# FanTimer.net
KiCad netlist of a schematic drawn in EAGLE
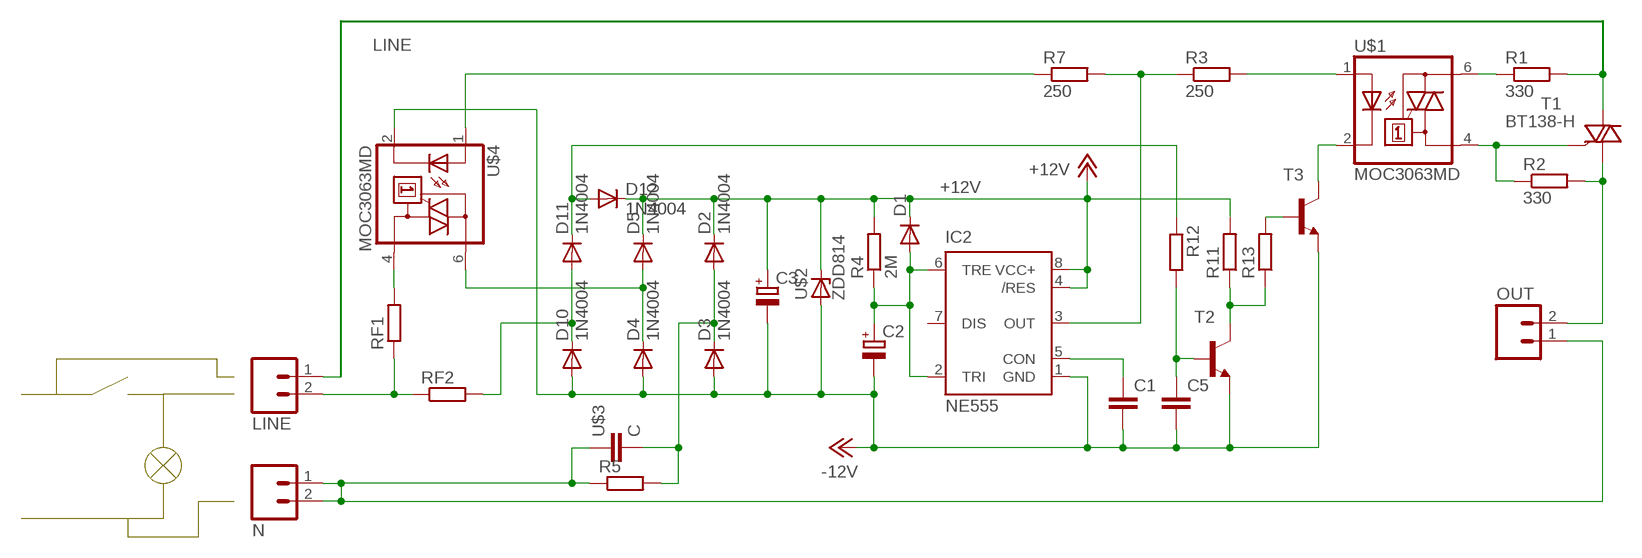
[diagram p0: schematic, sheet 1]

(export (version "E")
  (design (tool "Eeschema 10.0.6"))
  (components
    (comp (ref "C1")
      (value "C-EU050-025X075")
      (footprint "eagle-import:C050-025X075")
      (libsource (lib "eagle-import") (part "C-EU050-025X075"))
    )
    (comp (ref "C2")
      (value "CPOL-EUE2.5-7")
      (footprint "eagle-import:E2,5-7")
      (libsource (lib "eagle-import") (part "CPOL-EUE2.5-7"))
    )
    (comp (ref "C3")
      (value "CPOL-EUE2.5-7")
      (footprint "eagle-import:E2,5-7")
      (libsource (lib "eagle-import") (part "CPOL-EUE2.5-7"))
    )
    (comp (ref "C5")
      (value "C-EUC0805")
      (footprint "eagle-import:C0805")
      (libsource (lib "eagle-import") (part "C-EUC0805"))
    )
    (comp (ref "D1")
      (value "DIODE-SOD80C")
      (footprint "eagle-import:SOD80C")
      (libsource (lib "eagle-import") (part "DIODE-SOD80C"))
    )
    (comp (ref "D2")
      (value "1N4004")
      (footprint "eagle-import:DO41-10")
      (libsource (lib "eagle-import") (part "1N4004"))
    )
    (comp (ref "D3")
      (value "1N4004")
      (footprint "eagle-import:DO41-10")
      (libsource (lib "eagle-import") (part "1N4004"))
    )
    (comp (ref "D4")
      (value "1N4004")
      (footprint "eagle-import:DO41-10")
      (libsource (lib "eagle-import") (part "1N4004"))
    )
    (comp (ref "D5")
      (value "1N4004")
      (footprint "eagle-import:DO41-10")
      (libsource (lib "eagle-import") (part "1N4004"))
    )
    (comp (ref "D10")
      (value "1N4004")
      (footprint "eagle-import:DO41-10")
      (libsource (lib "eagle-import") (part "1N4004"))
    )
    (comp (ref "D11")
      (value "1N4004")
      (footprint "eagle-import:DO41-10")
      (libsource (lib "eagle-import") (part "1N4004"))
    )
    (comp (ref "D12")
      (value "1N4004")
      (footprint "eagle-import:DO41-10")
      (libsource (lib "eagle-import") (part "1N4004"))
    )
    (comp (ref "IC2")
      (value "NE555")
      (footprint "eagle-import:DIL-08")
      (fields (field (name "MF") "Arrow Electronics") (field (name "MPN") "NE555N"))
      (libsource (lib "eagle-import") (part "NE555"))
    )
    (comp (ref "LINE")
      (value "CON_2P")
      (footprint "eagle-import:CON_PWR_2PIN4MM")
      (libsource (lib "eagle-import") (part "CON_2P"))
    )
    (comp (ref "N")
      (value "CON_2P")
      (footprint "eagle-import:CON_PWR_2PIN4MM")
      (libsource (lib "eagle-import") (part "CON_2P"))
    )
    (comp (ref "OUT")
      (value "CON_2P")
      (footprint "eagle-import:CON_PWR_2PIN4MM")
      (libsource (lib "eagle-import") (part "CON_2P"))
    )
    (comp (ref "R1")
      (value "330")
      (footprint "eagle-import:0207_10")
      (libsource (lib "eagle-import") (part "R-EU_0207/10"))
    )
    (comp (ref "R2")
      (value "330")
      (footprint "eagle-import:0207_10")
      (libsource (lib "eagle-import") (part "R-EU_0207/10"))
    )
    (comp (ref "R3")
      (value "250")
      (footprint "eagle-import:0207_10")
      (libsource (lib "eagle-import") (part "R-EU_0207/10"))
    )
    (comp (ref "R4")
      (value "2M")
      (footprint "eagle-import:0207_10")
      (libsource (lib "eagle-import") (part "R-EU_0207/10"))
    )
    (comp (ref "R5")
      (value "R-EU_0411/12")
      (footprint "eagle-import:0411_12")
      (libsource (lib "eagle-import") (part "R-EU_0411/12"))
    )
    (comp (ref "R7")
      (value "250")
      (footprint "eagle-import:0207_10")
      (libsource (lib "eagle-import") (part "R-EU_0207/10"))
    )
    (comp (ref "R11")
      (value "R-EU_0207/10")
      (footprint "eagle-import:0207_10")
      (libsource (lib "eagle-import") (part "R-EU_0207/10"))
    )
    (comp (ref "R12")
      (value "R-EU_0207/10")
      (footprint "eagle-import:0207_10")
      (libsource (lib "eagle-import") (part "R-EU_0207/10"))
    )
    (comp (ref "R13")
      (value "R-EU_0207/10")
      (footprint "eagle-import:0207_10")
      (libsource (lib "eagle-import") (part "R-EU_0207/10"))
    )
    (comp (ref "RF1")
      (value "R-EU_R1206")
      (footprint "eagle-import:R1206")
      (libsource (lib "eagle-import") (part "R-EU_R1206"))
    )
    (comp (ref "RF2")
      (value "R-EU_R1206")
      (footprint "eagle-import:R1206")
      (libsource (lib "eagle-import") (part "R-EU_R1206"))
    )
    (comp (ref "T1")
      (value "BT138-H")
      (footprint "eagle-import:TO220BH")
      (libsource (lib "eagle-import") (part "BT138-H"))
    )
    (comp (ref "T2")
      (value "-NPN-TO92-ECB")
      (footprint "eagle-import:TO92-ECB")
      (libsource (lib "eagle-import") (part "-NPN-TO92-ECB"))
    )
    (comp (ref "T3")
      (value "-NPN-TO92-ECB")
      (footprint "eagle-import:TO92-ECB")
      (libsource (lib "eagle-import") (part "-NPN-TO92-ECB"))
    )
    (comp (ref "U$1")
      (value "MOC3063MD")
      (footprint "eagle-import:DIL6")
      (libsource (lib "eagle-import") (part "MOC3063MD"))
    )
    (comp (ref "U$2")
      (value "ZDD814")
      (footprint "eagle-import:ZDMETAL")
      (libsource (lib "eagle-import") (part "ZDD814"))
    )
    (comp (ref "U$3")
      (value "C")
      (footprint "eagle-import:C_22X10")
      (libsource (lib "eagle-import") (part "C"))
    )
    (comp (ref "U$4")
      (value "MOC3063MD")
      (footprint "eagle-import:DIL6")
      (libsource (lib "eagle-import") (part "MOC3063MD"))
    )
  )
  (nets
    (net (code "1") (name "+12V") (class "Default")
      (node (ref "C3") (pin "+") (pinfunction "+_+") (pintype "passive"))
      (node (ref "D1") (pin "C") (pinfunction "C_C") (pintype "passive"))
      (node (ref "D12") (pin "C") (pinfunction "C_C") (pintype "passive"))
      (node (ref "D2") (pin "C") (pinfunction "C_C") (pintype "passive"))
      (node (ref "D5") (pin "C") (pinfunction "C_C") (pintype "passive"))
      (node (ref "IC2") (pin "4") (pinfunction "/RES_4") (pintype "input"))
      (node (ref "IC2") (pin "8") (pinfunction "VCC+_8") (pintype "power_in"))
      (node (ref "R11") (pin "2") (pinfunction "2_2") (pintype "passive"))
      (node (ref "R4") (pin "2") (pinfunction "2_2") (pintype "passive"))
      (node (ref "U$2") (pin "C") (pinfunction "C_C") (pintype "passive"))
    )
    (net (code "2") (name "-12V") (class "Default")
      (node (ref "C1") (pin "2") (pinfunction "2_2") (pintype "passive"))
      (node (ref "C2") (pin "-") (pinfunction "-_-") (pintype "passive"))
      (node (ref "C3") (pin "-") (pinfunction "-_-") (pintype "passive"))
      (node (ref "C5") (pin "2") (pinfunction "2_2") (pintype "passive"))
      (node (ref "D10") (pin "A") (pinfunction "A_A") (pintype "passive"))
      (node (ref "D3") (pin "A") (pinfunction "A_A") (pintype "passive"))
      (node (ref "D4") (pin "A") (pinfunction "A_A") (pintype "passive"))
      (node (ref "IC2") (pin "1") (pinfunction "GND_1") (pintype "power_in"))
      (node (ref "T2") (pin "E") (pinfunction "E_E") (pintype "passive"))
      (node (ref "T3") (pin "E") (pinfunction "E_E") (pintype "passive"))
      (node (ref "U$2") (pin "A") (pinfunction "A_A") (pintype "passive"))
      (node (ref "U$4") (pin "2") (pinfunction "C_2") (pintype "passive"))
    )
    (net (code "3") (name "/LINE") (class "Default")
      (node (ref "LINE") (pin "1") (pinfunction "1_1") (pintype "passive"))
      (node (ref "R1") (pin "2") (pinfunction "2_2") (pintype "passive"))
      (node (ref "T1") (pin "T2") (pinfunction "A2_T2") (pintype "passive"))
    )
    (net (code "4") (name "Net-(C5-Pad1)") (class "Default")
      (node (ref "C5") (pin "1") (pinfunction "1_1") (pintype "passive"))
      (node (ref "R12") (pin "2") (pinfunction "2_2") (pintype "passive"))
      (node (ref "T2") (pin "B") (pinfunction "B_B") (pintype "passive"))
    )
    (net (code "5") (name "Net-(D2-PadA)") (class "Default")
      (node (ref "D2") (pin "A") (pinfunction "A_A") (pintype "passive"))
      (node (ref "D3") (pin "C") (pinfunction "C_C") (pintype "passive"))
      (node (ref "R5") (pin "2") (pinfunction "2_2") (pintype "passive"))
      (node (ref "U$3") (pin "2") (pinfunction "2_2") (pintype "passive"))
    )
    (net (code "6") (name "Net-(D10-PadC)") (class "Default")
      (node (ref "D10") (pin "C") (pinfunction "C_C") (pintype "passive"))
      (node (ref "D11") (pin "A") (pinfunction "A_A") (pintype "passive"))
      (node (ref "RF2") (pin "2") (pinfunction "2_2") (pintype "passive"))
    )
    (net (code "7") (name "Net-(D11-PadC)") (class "Default")
      (node (ref "D11") (pin "C") (pinfunction "C_C") (pintype "passive"))
      (node (ref "D12") (pin "A") (pinfunction "A_A") (pintype "passive"))
      (node (ref "R12") (pin "1") (pinfunction "1_1") (pintype "passive"))
    )
    (net (code "8") (name "Net-(IC2-CON)") (class "Default")
      (node (ref "C1") (pin "1") (pinfunction "1_1") (pintype "passive"))
      (node (ref "IC2") (pin "5") (pinfunction "CON_5") (pintype "input"))
    )
    (net (code "9") (name "Net-(IC2-OUT)") (class "Default")
      (node (ref "IC2") (pin "3") (pinfunction "OUT_3") (pintype "output"))
      (node (ref "R3") (pin "1") (pinfunction "1_1") (pintype "passive"))
      (node (ref "R7") (pin "2") (pinfunction "2_2") (pintype "passive"))
    )
    (net (code "10") (name "Net-(IC2-TRE)") (class "Default")
      (node (ref "C2") (pin "+") (pinfunction "+_+") (pintype "passive"))
      (node (ref "D1") (pin "A") (pinfunction "A_A") (pintype "passive"))
      (node (ref "IC2") (pin "2") (pinfunction "TRI_2") (pintype "input"))
      (node (ref "IC2") (pin "6") (pinfunction "TRE_6") (pintype "input"))
      (node (ref "R4") (pin "1") (pinfunction "1_1") (pintype "passive"))
    )
    (net (code "11") (name "Net-(LINE-Pad2)") (class "Default")
      (node (ref "LINE") (pin "2") (pinfunction "2_2") (pintype "passive"))
      (node (ref "RF1") (pin "1") (pinfunction "1_1") (pintype "passive"))
      (node (ref "RF2") (pin "1") (pinfunction "1_1") (pintype "passive"))
    )
    (net (code "12") (name "Net-(N-Pad1)") (class "Default")
      (node (ref "N") (pin "1") (pinfunction "1_1") (pintype "passive"))
      (node (ref "N") (pin "2") (pinfunction "2_2") (pintype "passive"))
      (node (ref "OUT") (pin "1") (pinfunction "1_1") (pintype "passive"))
      (node (ref "R5") (pin "1") (pinfunction "1_1") (pintype "passive"))
      (node (ref "U$3") (pin "1") (pinfunction "1_1") (pintype "passive"))
    )
    (net (code "13") (name "Net-(R11-Pad1)") (class "Default")
      (node (ref "R11") (pin "1") (pinfunction "1_1") (pintype "passive"))
      (node (ref "R13") (pin "1") (pinfunction "1_1") (pintype "passive"))
      (node (ref "T2") (pin "C") (pinfunction "C_C") (pintype "passive"))
    )
    (net (code "14") (name "Net-(R13-Pad2)") (class "Default")
      (node (ref "R13") (pin "2") (pinfunction "2_2") (pintype "passive"))
      (node (ref "T3") (pin "B") (pinfunction "B_B") (pintype "passive"))
    )
    (net (code "15") (name "Net-(T1-A1)") (class "Default")
      (node (ref "OUT") (pin "2") (pinfunction "2_2") (pintype "passive"))
      (node (ref "R2") (pin "2") (pinfunction "2_2") (pintype "passive"))
      (node (ref "T1") (pin "T1") (pinfunction "A1_T1") (pintype "passive"))
    )
    (net (code "16") (name "Net-(U$1-A)") (class "Default")
      (node (ref "R3") (pin "2") (pinfunction "2_2") (pintype "passive"))
      (node (ref "U$1") (pin "1") (pinfunction "A_1") (pintype "passive"))
    )
    (net (code "17") (name "Net-(U$1-A1)") (class "Default")
      (node (ref "R2") (pin "1") (pinfunction "1_1") (pintype "passive"))
      (node (ref "T1") (pin "G") (pinfunction "G_G") (pintype "passive"))
      (node (ref "U$1") (pin "4") (pinfunction "A1_4") (pintype "passive"))
    )
    (net (code "18") (name "Net-(U$1-A2)") (class "Default")
      (node (ref "R1") (pin "1") (pinfunction "1_1") (pintype "passive"))
      (node (ref "U$1") (pin "6") (pinfunction "A2_6") (pintype "passive"))
    )
    (net (code "19") (name "Net-(U$1-C)") (class "Default")
      (node (ref "T3") (pin "C") (pinfunction "C_C") (pintype "passive"))
      (node (ref "U$1") (pin "2") (pinfunction "C_2") (pintype "passive"))
    )
    (net (code "20") (name "Net-(U$4-A)") (class "Default")
      (node (ref "R7") (pin "1") (pinfunction "1_1") (pintype "passive"))
      (node (ref "U$4") (pin "1") (pinfunction "A_1") (pintype "passive"))
    )
    (net (code "21") (name "Net-(U$4-A1)") (class "Default")
      (node (ref "RF1") (pin "2") (pinfunction "2_2") (pintype "passive"))
      (node (ref "U$4") (pin "4") (pinfunction "A1_4") (pintype "passive"))
    )
    (net (code "22") (name "Net-(U$4-A2)") (class "Default")
      (node (ref "D4") (pin "C") (pinfunction "C_C") (pintype "passive"))
      (node (ref "D5") (pin "A") (pinfunction "A_A") (pintype "passive"))
      (node (ref "U$4") (pin "6") (pinfunction "A2_6") (pintype "passive"))
    )
    (net (code "23") (name "unconnected-(IC2-DIS-Pad7)") (class "Default")
      (node (ref "IC2") (pin "7") (pinfunction "DIS_7") (pintype "input"))
    )
  )
)
